# GPS_radiologger_v16.net
KiCad netlist of a schematic drawn in EAGLE
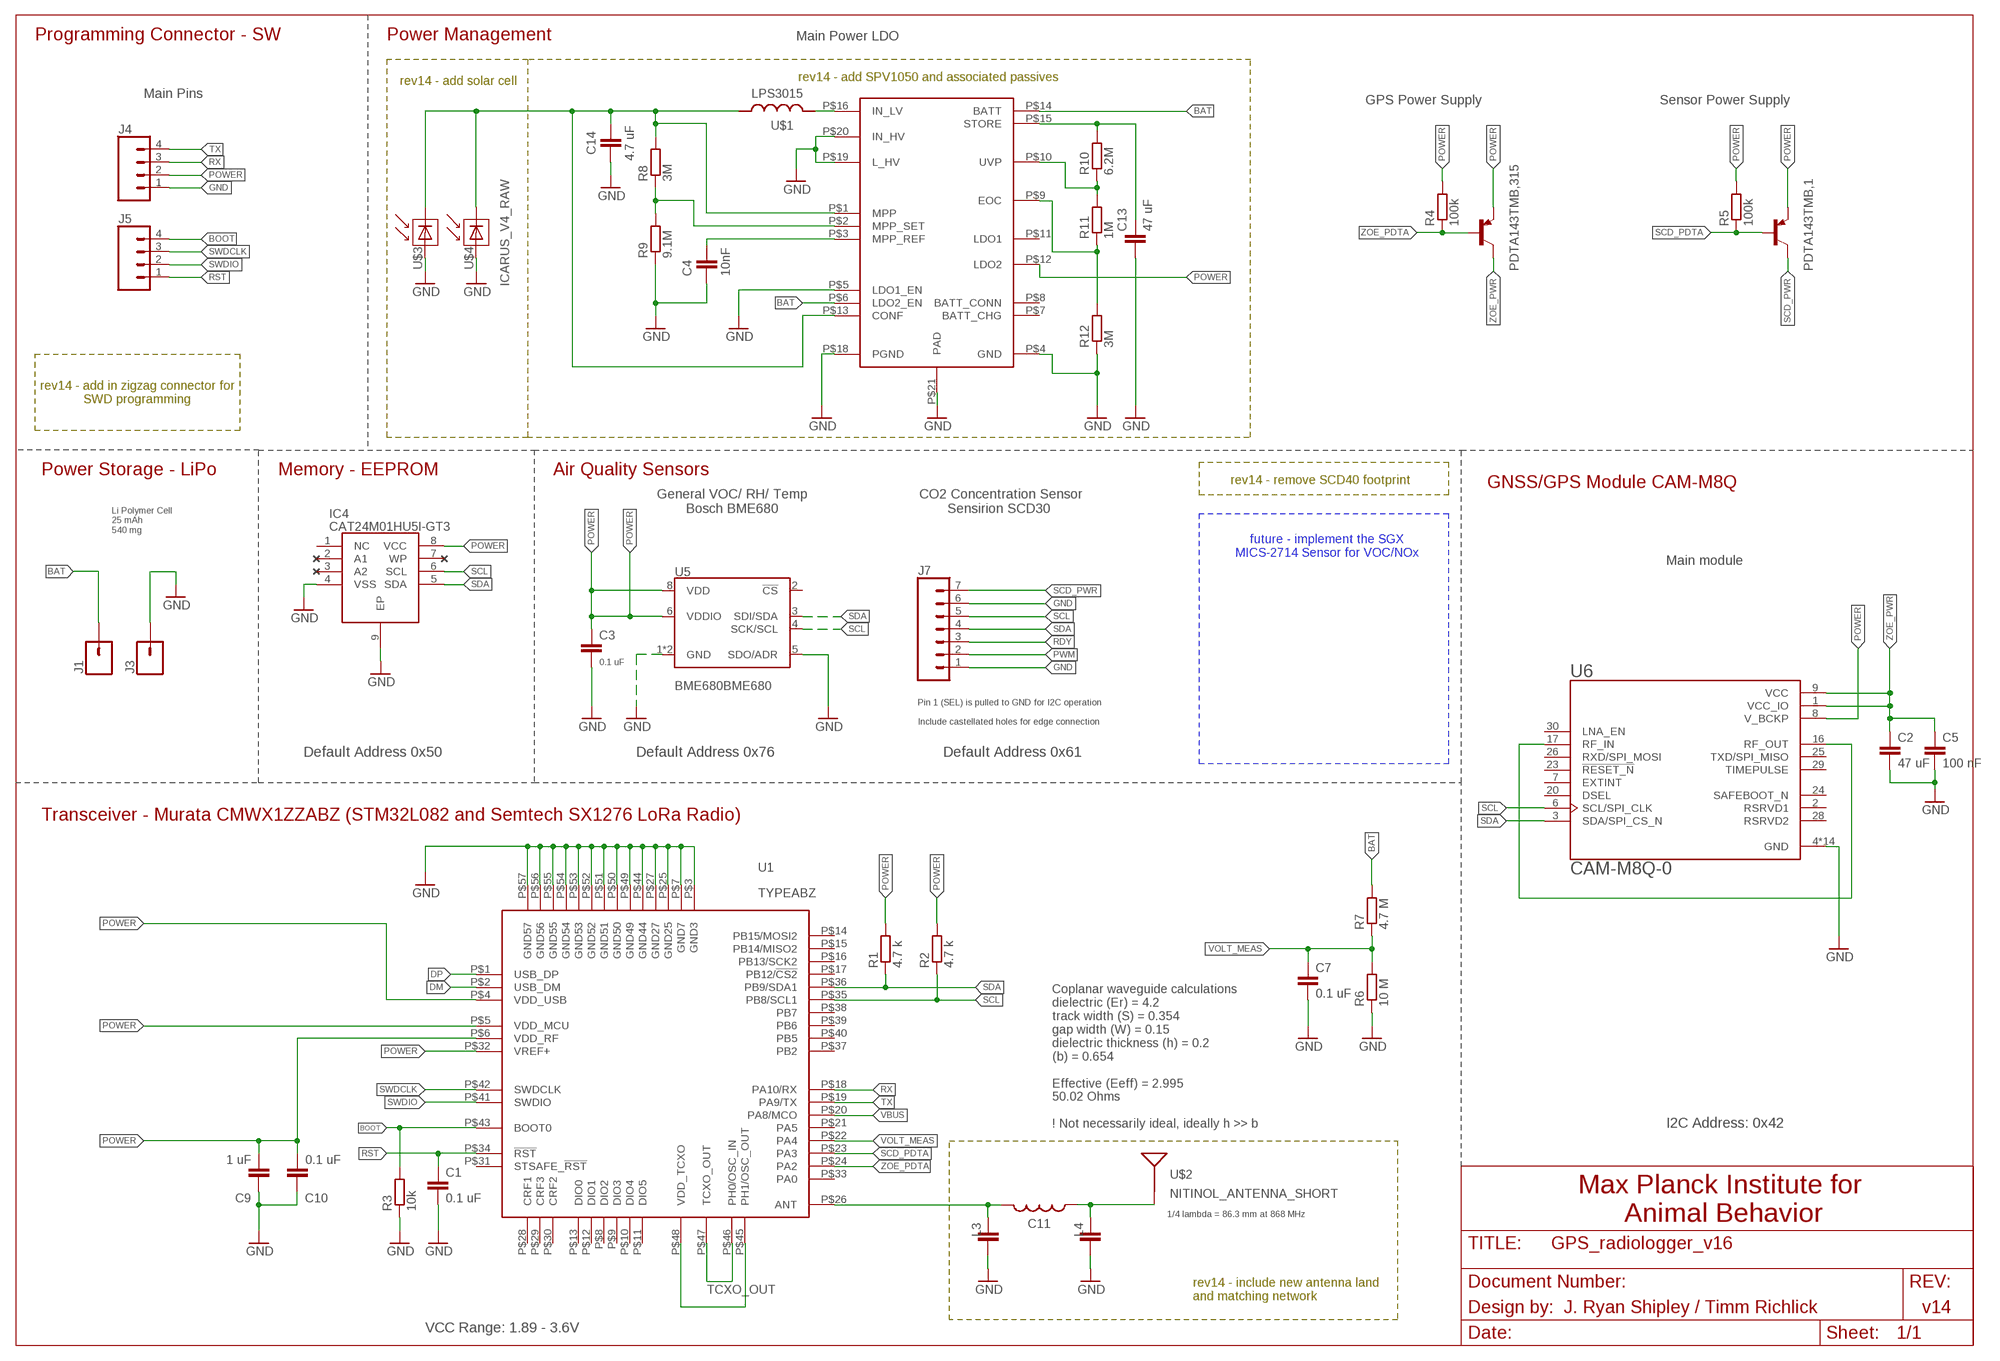
[diagram p0: schematic, sheet 1]

(export (version "E")
  (design (tool "Eeschema 10.0.6"))
  (components
    (comp (ref "C1")
      (value "0.1 uF")
      (footprint "eagle-import:C0201")
      (libsource (lib "eagle-import") (part "C-EUC0201"))
    )
    (comp (ref "C2")
      (value "47 uF")
      (footprint "eagle-import:C0201")
      (libsource (lib "eagle-import") (part "C-EUC0201"))
    )
    (comp (ref "C3")
      (value "0.1 uF")
      (footprint "eagle-import:C0201")
      (libsource (lib "eagle-import") (part "C-EUC0201"))
    )
    (comp (ref "C4")
      (value "10nF")
      (footprint "eagle-import:C0201")
      (libsource (lib "eagle-import") (part "C-EUC0201"))
    )
    (comp (ref "C5")
      (value "100 nF")
      (footprint "eagle-import:C0201")
      (libsource (lib "eagle-import") (part "C-EUC0201"))
    )
    (comp (ref "C7")
      (value "0.1 uF")
      (footprint "eagle-import:C0201")
      (libsource (lib "eagle-import") (part "C-EUC0201"))
    )
    (comp (ref "C9")
      (value "1 uF")
      (footprint "eagle-import:C0201")
      (libsource (lib "eagle-import") (part "C-EUC0201"))
    )
    (comp (ref "C10")
      (value "0.1 uF")
      (footprint "eagle-import:C0201")
      (libsource (lib "eagle-import") (part "C-EUC0201"))
    )
    (comp (ref "C11")
      (value "0.1uF")
      (footprint "eagle-import:L0201")
      (libsource (lib "eagle-import") (part "L-USL0201"))
    )
    (comp (ref "C13")
      (value "47 uF")
      (footprint "eagle-import:C0805K")
      (libsource (lib "eagle-import") (part "C-EUC0805K"))
    )
    (comp (ref "C14")
      (value "4.7 uF")
      (footprint "eagle-import:C0201")
      (libsource (lib "eagle-import") (part "C-EUC0201"))
    )
    (comp (ref "IC4")
      (value "CAT24M01HU5I-GT3")
      (footprint "eagle-import:SON50P300X200X55-9N")
      (fields
        (field (name "MOUSER_PART_NUMBER") "863-CAT24M01HU5I-GT3")
        (field (name "RS_PART_NUMBER") "7814831P")
      )
      (libsource (lib "eagle-import") (part "CAT24M01HU5I-GT3"))
    )
    (comp (ref "J1")
      (value "CONN_01PTH_NO_SILK_YES_STOP")
      (footprint "eagle-import:1X01_NO_SILK")
      (libsource (lib "eagle-import") (part "CONN_01PTH_NO_SILK_YES_STOP"))
    )
    (comp (ref "J3")
      (value "CONN_01PTH_NO_SILK_YES_STOP")
      (footprint "eagle-import:1X01_NO_SILK")
      (libsource (lib "eagle-import") (part "CONN_01PTH_NO_SILK_YES_STOP"))
    )
    (comp (ref "J4")
      (value "CONN_041.27MM_NO_SILK")
      (footprint "eagle-import:1X04_1.27MM_NO_SILK")
      (libsource (lib "eagle-import") (part "CONN_041.27MM_NO_SILK"))
    )
    (comp (ref "J5")
      (value "CONN_041.27MM_NO_SILK")
      (footprint "eagle-import:1X04_1.27MM_NO_SILK")
      (libsource (lib "eagle-import") (part "CONN_041.27MM_NO_SILK"))
    )
    (comp (ref "J7")
      (value "CONN_07NO_SILK")
      (footprint "eagle-import:1X07_NO_SILK")
      (libsource (lib "eagle-import") (part "CONN_07NO_SILK"))
    )
    (comp (ref "L3")
      (value "C-EUC0201")
      (footprint "eagle-import:C0201")
      (libsource (lib "eagle-import") (part "C-EUC0201"))
    )
    (comp (ref "L4")
      (value "C-EUC0201")
      (footprint "eagle-import:C0201")
      (libsource (lib "eagle-import") (part "C-EUC0201"))
    )
    (comp (ref "PDTA143TMB,1")
      (value "TINYPICO-PNPAMB")
      (footprint "eagle-import:SOT883(B)")
      (libsource (lib "eagle-import") (part "TINYPICO-PNPMBA"))
    )
    (comp (ref "PDTA143TMB,315")
      (value "TINYPICO-PNPAMB")
      (footprint "eagle-import:SOT883(B)")
      (libsource (lib "eagle-import") (part "TINYPICO-PNPMBA"))
    )
    (comp (ref "R1")
      (value "4.7 k")
      (footprint "eagle-import:R0201")
      (libsource (lib "eagle-import") (part "R-EU_R0201"))
    )
    (comp (ref "R2")
      (value "4.7 k")
      (footprint "eagle-import:R0201")
      (libsource (lib "eagle-import") (part "R-EU_R0201"))
    )
    (comp (ref "R3")
      (value "10k")
      (footprint "eagle-import:R0201")
      (libsource (lib "eagle-import") (part "R-EU_R0201"))
    )
    (comp (ref "R4")
      (value "100k")
      (footprint "eagle-import:R0201")
      (libsource (lib "eagle-import") (part "R-EU_R0201"))
    )
    (comp (ref "R5")
      (value "100k")
      (footprint "eagle-import:R0201")
      (libsource (lib "eagle-import") (part "R-EU_R0201"))
    )
    (comp (ref "R6")
      (value "10 M")
      (footprint "eagle-import:R0201")
      (libsource (lib "eagle-import") (part "R-EU_R0201"))
    )
    (comp (ref "R7")
      (value "4.7 M")
      (footprint "eagle-import:R0201")
      (libsource (lib "eagle-import") (part "R-EU_R0201"))
    )
    (comp (ref "R8")
      (value "3M")
      (footprint "eagle-import:R0201")
      (libsource (lib "eagle-import") (part "R-EU_R0201"))
    )
    (comp (ref "R9")
      (value "9.1M")
      (footprint "eagle-import:R0201")
      (libsource (lib "eagle-import") (part "R-EU_R0201"))
    )
    (comp (ref "R10")
      (value "6.2M")
      (footprint "eagle-import:R0201")
      (libsource (lib "eagle-import") (part "R-EU_R0201"))
    )
    (comp (ref "R11")
      (value "1M")
      (footprint "eagle-import:R0201")
      (libsource (lib "eagle-import") (part "R-EU_R0201"))
    )
    (comp (ref "R12")
      (value "3M")
      (footprint "eagle-import:R0201")
      (libsource (lib "eagle-import") (part "R-EU_R0201"))
    )
    (comp (ref "U$1")
      (value "LPS3015")
      (footprint "eagle-import:LPS_3015")
      (libsource (lib "eagle-import") (part "LPS3015"))
    )
    (comp (ref "U$2")
      (value "NITINOL_ANTENNA_SHORT")
      (footprint "eagle-import:ICARUS_NITINOL_ANTENNA_SHORT")
      (libsource (lib "eagle-import") (part "NITINOL_ANTENNA_SHORT"))
    )
    (comp (ref "U$3")
      (value "ICARUS_V4_RAW")
      (footprint "eagle-import:ICARUS_FULL_TOP")
      (libsource (lib "eagle-import") (part "ICARUS_V4_RAW"))
    )
    (comp (ref "U$4")
      (value "ICARUS_V4_RAW")
      (footprint "eagle-import:ICARUS_FULL_TOP")
      (libsource (lib "eagle-import") (part "ICARUS_V4_RAW"))
    )
    (comp (ref "U1")
      (value "TYPEABZ")
      (footprint "eagle-import:TYPEABZ")
      (libsource (lib "eagle-import") (part "TYPEABZ"))
    )
    (comp (ref "U4")
      (value "SPV1050")
      (footprint "eagle-import:SPV1050")
      (libsource (lib "eagle-import") (part "SPV1050"))
    )
    (comp (ref "U5")
      (value "BME680BME680")
      (footprint "eagle-import:LGA3.0X3.0")
      (libsource (lib "eagle-import") (part "BME680BME680"))
    )
    (comp (ref "U6")
      (value "CAM-M8Q-0")
      (footprint "eagle-import:LCC100P960X1400X210-31N")
      (fields (field (name "MF") "U-Blox America"))
      (libsource (lib "eagle-import") (part "CAM-M8Q-0"))
    )
  )
  (nets
    (net (code "1") (name "/TCXO_OUT") (class "Default")
      (node (ref "U1") (pin "P$46") (pinfunction "PH0/OSC_IN_P$46") (pintype "bidirectional"))
      (node (ref "U1") (pin "P$47") (pinfunction "TCXO_OUT_P$47") (pintype "bidirectional"))
    )
    (net (code "2") (name "BAT") (class "Default")
      (node (ref "J1") (pin "1") (pinfunction "1_1") (pintype "passive"))
      (node (ref "R7") (pin "2") (pinfunction "2_2") (pintype "passive"))
      (node (ref "U4") (pin "P$14") (pinfunction "BATT_P$14") (pintype "bidirectional"))
      (node (ref "U4") (pin "P$6") (pinfunction "LDO2_EN_P$6") (pintype "input"))
    )
    (net (code "3") (name "BOOT") (class "Default")
      (node (ref "J5") (pin "4") (pinfunction "4_4") (pintype "passive"))
      (node (ref "R3") (pin "2") (pinfunction "2_2") (pintype "passive"))
      (node (ref "U1") (pin "P$43") (pinfunction "BOOT0_P$43") (pintype "bidirectional"))
    )
    (net (code "4") (name "DM") (class "Default")
      (node (ref "U1") (pin "P$2") (pinfunction "USB_DM_P$2") (pintype "bidirectional"))
    )
    (net (code "5") (name "DP") (class "Default")
      (node (ref "U1") (pin "P$1") (pinfunction "USB_DP_P$1") (pintype "bidirectional"))
    )
    (net (code "6") (name "GND") (class "Default")
      (node (ref "C1") (pin "2") (pinfunction "2_2") (pintype "passive"))
      (node (ref "C10") (pin "1") (pinfunction "1_1") (pintype "passive"))
      (node (ref "C13") (pin "2") (pinfunction "2_2") (pintype "passive"))
      (node (ref "C14") (pin "2") (pinfunction "2_2") (pintype "passive"))
      (node (ref "C2") (pin "2") (pinfunction "2_2") (pintype "passive"))
      (node (ref "C3") (pin "2") (pinfunction "2_2") (pintype "passive"))
      (node (ref "C4") (pin "2") (pinfunction "2_2") (pintype "passive"))
      (node (ref "C5") (pin "2") (pinfunction "2_2") (pintype "passive"))
      (node (ref "C7") (pin "2") (pinfunction "2_2") (pintype "passive"))
      (node (ref "C9") (pin "1") (pinfunction "1_1") (pintype "passive"))
      (node (ref "IC4") (pin "4") (pinfunction "VSS_4") (pintype "power_in"))
      (node (ref "IC4") (pin "9") (pinfunction "EP_9") (pintype "bidirectional"))
      (node (ref "J3") (pin "1") (pinfunction "1_1") (pintype "passive"))
      (node (ref "J4") (pin "1") (pinfunction "1_1") (pintype "passive"))
      (node (ref "J7") (pin "1") (pinfunction "1_1") (pintype "passive"))
      (node (ref "J7") (pin "6") (pinfunction "6_6") (pintype "passive"))
      (node (ref "L3") (pin "2") (pinfunction "2_2") (pintype "passive"))
      (node (ref "L4") (pin "2") (pinfunction "2_2") (pintype "passive"))
      (node (ref "R12") (pin "1") (pinfunction "1_1") (pintype "passive"))
      (node (ref "R3") (pin "1") (pinfunction "1_1") (pintype "passive"))
      (node (ref "R6") (pin "1") (pinfunction "1_1") (pintype "passive"))
      (node (ref "R9") (pin "1") (pinfunction "1_1") (pintype "passive"))
      (node (ref "U$3") (pin "P$2") (pinfunction "MINUS_P$2") (pintype "passive"))
      (node (ref "U$4") (pin "P$2") (pinfunction "MINUS_P$2") (pintype "passive"))
      (node (ref "U1") (pin "P$25") (pinfunction "GND25_P$25") (pintype "power_in"))
      (node (ref "U1") (pin "P$27") (pinfunction "GND27_P$27") (pintype "power_in"))
      (node (ref "U1") (pin "P$3") (pinfunction "GND3_P$3") (pintype "power_in"))
      (node (ref "U1") (pin "P$44") (pinfunction "GND44_P$44") (pintype "power_in"))
      (node (ref "U1") (pin "P$49") (pinfunction "GND49_P$49") (pintype "power_in"))
      (node (ref "U1") (pin "P$50") (pinfunction "GND50_P$50") (pintype "power_in"))
      (node (ref "U1") (pin "P$51") (pinfunction "GND51_P$51") (pintype "power_in"))
      (node (ref "U1") (pin "P$52") (pinfunction "GND52_P$52") (pintype "power_in"))
      (node (ref "U1") (pin "P$53") (pinfunction "GND53_P$53") (pintype "power_in"))
      (node (ref "U1") (pin "P$54") (pinfunction "GND54_P$54") (pintype "power_in"))
      (node (ref "U1") (pin "P$55") (pinfunction "GND55_P$55") (pintype "power_in"))
      (node (ref "U1") (pin "P$56") (pinfunction "GND56_P$56") (pintype "power_in"))
      (node (ref "U1") (pin "P$57") (pinfunction "GND57_P$57") (pintype "power_in"))
      (node (ref "U1") (pin "P$7") (pinfunction "GND7_P$7") (pintype "power_in"))
      (node (ref "U4") (pin "P$18") (pinfunction "PGND_P$18") (pintype "power_in"))
      (node (ref "U4") (pin "P$19") (pinfunction "L_HV_P$19") (pintype "power_in"))
      (node (ref "U4") (pin "P$20") (pinfunction "IN_HV_P$20") (pintype "power_in"))
      (node (ref "U4") (pin "P$21") (pinfunction "PAD_P$21") (pintype "power_in"))
      (node (ref "U4") (pin "P$4") (pinfunction "GND_P$4") (pintype "power_in"))
      (node (ref "U4") (pin "P$5") (pinfunction "LDO1_EN_P$5") (pintype "input"))
      (node (ref "U5") (pin "1") (pinfunction "GND_1") (pintype "bidirectional"))
      (node (ref "U5") (pin "5") (pinfunction "SDO/ADR_5") (pintype "bidirectional"))
      (node (ref "U5") (pin "7") (pinfunction "GND_7") (pintype "bidirectional"))
      (node (ref "U6") (pin "10") (pinfunction "GND_10") (pintype "power_in"))
      (node (ref "U6") (pin "11") (pinfunction "GND_11") (pintype "power_in"))
      (node (ref "U6") (pin "12") (pinfunction "GND_12") (pintype "power_in"))
      (node (ref "U6") (pin "13") (pinfunction "GND_13") (pintype "power_in"))
      (node (ref "U6") (pin "14") (pinfunction "GND_14") (pintype "power_in"))
      (node (ref "U6") (pin "15") (pinfunction "GND_15") (pintype "power_in"))
      (node (ref "U6") (pin "18") (pinfunction "GND_18") (pintype "power_in"))
      (node (ref "U6") (pin "19") (pinfunction "GND_19") (pintype "power_in"))
      (node (ref "U6") (pin "21") (pinfunction "GND_21") (pintype "power_in"))
      (node (ref "U6") (pin "22") (pinfunction "GND_22") (pintype "power_in"))
      (node (ref "U6") (pin "27") (pinfunction "GND_27") (pintype "power_in"))
      (node (ref "U6") (pin "31") (pinfunction "GND_31") (pintype "power_in"))
      (node (ref "U6") (pin "4") (pinfunction "GND_4") (pintype "power_in"))
      (node (ref "U6") (pin "5") (pinfunction "GND_5") (pintype "power_in"))
    )
    (net (code "7") (name "Net-(C11-Pad1)") (class "Default")
      (node (ref "C11") (pin "1") (pinfunction "1_1") (pintype "passive"))
      (node (ref "L4") (pin "1") (pinfunction "1_1") (pintype "passive"))
      (node (ref "U$2") (pin "1") (pinfunction "SIGNAL_1") (pintype "bidirectional"))
      (node (ref "U$2") (pin "2") (pinfunction "SIGNAL_2") (pintype "bidirectional"))
      (node (ref "U$2") (pin "3") (pinfunction "SIGNAL_3") (pintype "bidirectional"))
    )
    (net (code "8") (name "Net-(U$1-1)") (class "Default")
      (node (ref "C14") (pin "1") (pinfunction "1_1") (pintype "passive"))
      (node (ref "R8") (pin "2") (pinfunction "2_2") (pintype "passive"))
      (node (ref "U$1") (pin "P$1") (pinfunction "1_P$1") (pintype "passive"))
      (node (ref "U$3") (pin "P$1") (pinfunction "PLUS_P$1") (pintype "passive"))
      (node (ref "U$4") (pin "P$1") (pinfunction "PLUS_P$1") (pintype "passive"))
      (node (ref "U4") (pin "P$1") (pinfunction "MPP_P$1") (pintype "input"))
      (node (ref "U4") (pin "P$13") (pinfunction "CONF_P$13") (pintype "input"))
    )
    (net (code "9") (name "Net-(U$1-2)") (class "Default")
      (node (ref "U$1") (pin "P$2") (pinfunction "2_P$2") (pintype "passive"))
      (node (ref "U4") (pin "P$16") (pinfunction "IN_LV_P$16") (pintype "power_in"))
    )
    (net (code "10") (name "Net-(U1-ANT)") (class "Default")
      (node (ref "C11") (pin "2") (pinfunction "2_2") (pintype "passive"))
      (node (ref "L3") (pin "1") (pinfunction "1_1") (pintype "passive"))
      (node (ref "U1") (pin "P$26") (pinfunction "ANT_P$26") (pintype "bidirectional"))
    )
    (net (code "11") (name "Net-(U1-PH1{slash}OSC_OUT)") (class "Default")
      (node (ref "U1") (pin "P$45") (pinfunction "PH1/OSC_OUT_P$45") (pintype "bidirectional"))
      (node (ref "U1") (pin "P$48") (pinfunction "VDD_TCXO_P$48") (pintype "power_in"))
    )
    (net (code "12") (name "Net-(U4-EOC)") (class "Default")
      (node (ref "R11") (pin "1") (pinfunction "1_1") (pintype "passive"))
      (node (ref "R12") (pin "2") (pinfunction "2_2") (pintype "passive"))
      (node (ref "U4") (pin "P$9") (pinfunction "EOC_P$9") (pintype "input"))
    )
    (net (code "13") (name "Net-(U4-MPP_REF)") (class "Default")
      (node (ref "C4") (pin "1") (pinfunction "1_1") (pintype "passive"))
      (node (ref "U4") (pin "P$3") (pinfunction "MPP_REF_P$3") (pintype "input"))
    )
    (net (code "14") (name "Net-(U4-MPP_SET)") (class "Default")
      (node (ref "R8") (pin "1") (pinfunction "1_1") (pintype "passive"))
      (node (ref "R9") (pin "2") (pinfunction "2_2") (pintype "passive"))
      (node (ref "U4") (pin "P$2") (pinfunction "MPP_SET_P$2") (pintype "input"))
    )
    (net (code "15") (name "Net-(U4-STORE)") (class "Default")
      (node (ref "C13") (pin "1") (pinfunction "1_1") (pintype "passive"))
      (node (ref "R10") (pin "2") (pinfunction "2_2") (pintype "passive"))
      (node (ref "U4") (pin "P$15") (pinfunction "STORE_P$15") (pintype "bidirectional"))
    )
    (net (code "16") (name "Net-(U4-UVP)") (class "Default")
      (node (ref "R10") (pin "1") (pinfunction "1_1") (pintype "passive"))
      (node (ref "R11") (pin "2") (pinfunction "2_2") (pintype "passive"))
      (node (ref "U4") (pin "P$10") (pinfunction "UVP_P$10") (pintype "input"))
    )
    (net (code "17") (name "Net-(U6-RF_IN)") (class "Default")
      (node (ref "U6") (pin "16") (pinfunction "RF_OUT_16") (pintype "output"))
      (node (ref "U6") (pin "17") (pinfunction "RF_IN_17") (pintype "input"))
    )
    (net (code "18") (name "POWER") (class "Default")
      (node (ref "C10") (pin "2") (pinfunction "2_2") (pintype "passive"))
      (node (ref "C3") (pin "1") (pinfunction "1_1") (pintype "passive"))
      (node (ref "C9") (pin "2") (pinfunction "2_2") (pintype "passive"))
      (node (ref "IC4") (pin "8") (pinfunction "VCC_8") (pintype "power_in"))
      (node (ref "J4") (pin "2") (pinfunction "2_2") (pintype "passive"))
      (node (ref "PDTA143TMB,1") (pin "2") (pinfunction "E_2") (pintype "passive"))
      (node (ref "PDTA143TMB,315") (pin "2") (pinfunction "E_2") (pintype "passive"))
      (node (ref "R1") (pin "2") (pinfunction "2_2") (pintype "passive"))
      (node (ref "R2") (pin "2") (pinfunction "2_2") (pintype "passive"))
      (node (ref "R4") (pin "2") (pinfunction "2_2") (pintype "passive"))
      (node (ref "R5") (pin "2") (pinfunction "2_2") (pintype "passive"))
      (node (ref "U1") (pin "P$32") (pinfunction "VREF+_P$32") (pintype "power_in"))
      (node (ref "U1") (pin "P$4") (pinfunction "VDD_USB_P$4") (pintype "power_in"))
      (node (ref "U1") (pin "P$5") (pinfunction "VDD_MCU_P$5") (pintype "power_in"))
      (node (ref "U1") (pin "P$6") (pinfunction "VDD_RF_P$6") (pintype "power_in"))
      (node (ref "U4") (pin "P$12") (pinfunction "LDO2_P$12") (pintype "output"))
      (node (ref "U5") (pin "6") (pinfunction "VDDIO_6") (pintype "bidirectional"))
      (node (ref "U5") (pin "8") (pinfunction "VDD_8") (pintype "bidirectional"))
      (node (ref "U6") (pin "8") (pinfunction "V_BCKP_8") (pintype "power_in"))
    )
    (net (code "19") (name "PWM") (class "Default")
      (node (ref "J7") (pin "2") (pinfunction "2_2") (pintype "passive"))
    )
    (net (code "20") (name "RDY") (class "Default")
      (node (ref "J7") (pin "3") (pinfunction "3_3") (pintype "passive"))
    )
    (net (code "21") (name "RST") (class "Default")
      (node (ref "C1") (pin "1") (pinfunction "1_1") (pintype "passive"))
      (node (ref "J5") (pin "1") (pinfunction "1_1") (pintype "passive"))
      (node (ref "U1") (pin "P$34") (pinfunction "~{RST}_P$34") (pintype "bidirectional"))
    )
    (net (code "22") (name "RX") (class "Default")
      (node (ref "J4") (pin "3") (pinfunction "3_3") (pintype "passive"))
      (node (ref "U1") (pin "P$18") (pinfunction "PA10/RX_P$18") (pintype "bidirectional"))
    )
    (net (code "23") (name "SCD_PDTA") (class "Default")
      (node (ref "PDTA143TMB,1") (pin "1") (pinfunction "B_1") (pintype "passive"))
      (node (ref "R5") (pin "1") (pinfunction "1_1") (pintype "passive"))
      (node (ref "U1") (pin "P$23") (pinfunction "PA3_P$23") (pintype "bidirectional"))
    )
    (net (code "24") (name "SCD_PWR") (class "Default")
      (node (ref "J7") (pin "7") (pinfunction "7_7") (pintype "passive"))
      (node (ref "PDTA143TMB,1") (pin "3") (pinfunction "C_3") (pintype "passive"))
    )
    (net (code "25") (name "SCL") (class "Default")
      (node (ref "IC4") (pin "6") (pinfunction "SCL_6") (pintype "bidirectional"))
      (node (ref "J7") (pin "5") (pinfunction "5_5") (pintype "passive"))
      (node (ref "R2") (pin "1") (pinfunction "1_1") (pintype "passive"))
      (node (ref "U1") (pin "P$35") (pinfunction "PB8/SCL1_P$35") (pintype "bidirectional"))
      (node (ref "U5") (pin "4") (pinfunction "SCK/SCL_4") (pintype "bidirectional"))
      (node (ref "U6") (pin "6") (pinfunction "SCL/SPI_CLK_6") (pintype "input"))
    )
    (net (code "26") (name "SDA") (class "Default")
      (node (ref "IC4") (pin "5") (pinfunction "SDA_5") (pintype "bidirectional"))
      (node (ref "J7") (pin "4") (pinfunction "4_4") (pintype "passive"))
      (node (ref "R1") (pin "1") (pinfunction "1_1") (pintype "passive"))
      (node (ref "U1") (pin "P$36") (pinfunction "PB9/SDA1_P$36") (pintype "bidirectional"))
      (node (ref "U5") (pin "3") (pinfunction "SDI/SDA_3") (pintype "bidirectional"))
      (node (ref "U6") (pin "3") (pinfunction "SDA/SPI_CS_N_3") (pintype "bidirectional"))
    )
    (net (code "27") (name "SWDCLK") (class "Default")
      (node (ref "J5") (pin "3") (pinfunction "3_3") (pintype "passive"))
      (node (ref "U1") (pin "P$42") (pinfunction "SWDCLK_P$42") (pintype "bidirectional"))
    )
    (net (code "28") (name "SWDIO") (class "Default")
      (node (ref "J5") (pin "2") (pinfunction "2_2") (pintype "passive"))
      (node (ref "U1") (pin "P$41") (pinfunction "SWDIO_P$41") (pintype "bidirectional"))
    )
    (net (code "29") (name "TX") (class "Default")
      (node (ref "J4") (pin "4") (pinfunction "4_4") (pintype "passive"))
      (node (ref "U1") (pin "P$19") (pinfunction "PA9/TX_P$19") (pintype "bidirectional"))
    )
    (net (code "30") (name "VBUS") (class "Default")
      (node (ref "U1") (pin "P$20") (pinfunction "PA8/MCO_P$20") (pintype "bidirectional"))
    )
    (net (code "31") (name "VOLT_MEAS") (class "Default")
      (node (ref "C7") (pin "1") (pinfunction "1_1") (pintype "passive"))
      (node (ref "R6") (pin "2") (pinfunction "2_2") (pintype "passive"))
      (node (ref "R7") (pin "1") (pinfunction "1_1") (pintype "passive"))
      (node (ref "U1") (pin "P$22") (pinfunction "PA4_P$22") (pintype "bidirectional"))
    )
    (net (code "32") (name "ZOE_PDTA") (class "Default")
      (node (ref "PDTA143TMB,315") (pin "1") (pinfunction "B_1") (pintype "passive"))
      (node (ref "R4") (pin "1") (pinfunction "1_1") (pintype "passive"))
      (node (ref "U1") (pin "P$24") (pinfunction "PA2_P$24") (pintype "bidirectional"))
    )
    (net (code "33") (name "ZOE_PWR") (class "Default")
      (node (ref "C2") (pin "1") (pinfunction "1_1") (pintype "passive"))
      (node (ref "C5") (pin "1") (pinfunction "1_1") (pintype "passive"))
      (node (ref "PDTA143TMB,315") (pin "3") (pinfunction "C_3") (pintype "passive"))
      (node (ref "U6") (pin "1") (pinfunction "VCC_IO_1") (pintype "power_in"))
      (node (ref "U6") (pin "9") (pinfunction "VCC_9") (pintype "power_in"))
    )
    (net (code "34") (name "unconnected-(IC4-A1-Pad2)") (class "Default")
      (node (ref "IC4") (pin "2") (pinfunction "A1_2") (pintype "bidirectional"))
    )
    (net (code "35") (name "unconnected-(IC4-A2-Pad3)") (class "Default")
      (node (ref "IC4") (pin "3") (pinfunction "A2_3") (pintype "bidirectional"))
    )
    (net (code "36") (name "unconnected-(IC4-NC-Pad1)") (class "Default")
      (node (ref "IC4") (pin "1") (pinfunction "NC_1") (pintype "no_connect"))
    )
    (net (code "37") (name "unconnected-(IC4-WP-Pad7)") (class "Default")
      (node (ref "IC4") (pin "7") (pinfunction "WP_7") (pintype "bidirectional"))
    )
    (net (code "38") (name "unconnected-(U1-CRF1-PadP$28)") (class "Default")
      (node (ref "U1") (pin "P$28") (pinfunction "CRF1_P$28") (pintype "no_connect"))
    )
    (net (code "39") (name "unconnected-(U1-CRF2-PadP$30)") (class "Default")
      (node (ref "U1") (pin "P$30") (pinfunction "CRF2_P$30") (pintype "no_connect"))
    )
    (net (code "40") (name "unconnected-(U1-CRF3-PadP$29)") (class "Default")
      (node (ref "U1") (pin "P$29") (pinfunction "CRF3_P$29") (pintype "no_connect"))
    )
    (net (code "41") (name "unconnected-(U1-DIO0-PadP$13)") (class "Default")
      (node (ref "U1") (pin "P$13") (pinfunction "DIO0_P$13") (pintype "no_connect"))
    )
    (net (code "42") (name "unconnected-(U1-DIO1-PadP$12)") (class "Default")
      (node (ref "U1") (pin "P$12") (pinfunction "DIO1_P$12") (pintype "no_connect"))
    )
    (net (code "43") (name "unconnected-(U1-DIO2-PadP$8)") (class "Default")
      (node (ref "U1") (pin "P$8") (pinfunction "DIO2_P$8") (pintype "no_connect"))
    )
    (net (code "44") (name "unconnected-(U1-DIO3-PadP$9)") (class "Default")
      (node (ref "U1") (pin "P$9") (pinfunction "DIO3_P$9") (pintype "no_connect"))
    )
    (net (code "45") (name "unconnected-(U1-DIO4-PadP$10)") (class "Default")
      (node (ref "U1") (pin "P$10") (pinfunction "DIO4_P$10") (pintype "bidirectional"))
    )
    (net (code "46") (name "unconnected-(U1-DIO5-PadP$11)") (class "Default")
      (node (ref "U1") (pin "P$11") (pinfunction "DIO5_P$11") (pintype "bidirectional"))
    )
    (net (code "47") (name "unconnected-(U1-PA0-PadP$33)") (class "Default")
      (node (ref "U1") (pin "P$33") (pinfunction "PA0_P$33") (pintype "bidirectional"))
    )
    (net (code "48") (name "unconnected-(U1-PA5-PadP$21)") (class "Default")
      (node (ref "U1") (pin "P$21") (pinfunction "PA5_P$21") (pintype "bidirectional"))
    )
    (net (code "49") (name "unconnected-(U1-PB2-PadP$37)") (class "Default")
      (node (ref "U1") (pin "P$37") (pinfunction "PB2_P$37") (pintype "bidirectional"))
    )
    (net (code "50") (name "unconnected-(U1-PB5-PadP$40)") (class "Default")
      (node (ref "U1") (pin "P$40") (pinfunction "PB5_P$40") (pintype "bidirectional"))
    )
    (net (code "51") (name "unconnected-(U1-PB6-PadP$39)") (class "Default")
      (node (ref "U1") (pin "P$39") (pinfunction "PB6_P$39") (pintype "bidirectional"))
    )
    (net (code "52") (name "unconnected-(U1-PB7-PadP$38)") (class "Default")
      (node (ref "U1") (pin "P$38") (pinfunction "PB7_P$38") (pintype "bidirectional"))
    )
    (net (code "53") (name "unconnected-(U1-PB12{slash}~{CS2}-PadP$17)") (class "Default")
      (node (ref "U1") (pin "P$17") (pinfunction "PB12/~{CS2}_P$17") (pintype "bidirectional"))
    )
    (net (code "54") (name "unconnected-(U1-PB13{slash}SCK2-PadP$16)") (class "Default")
      (node (ref "U1") (pin "P$16") (pinfunction "PB13/SCK2_P$16") (pintype "bidirectional"))
    )
    (net (code "55") (name "unconnected-(U1-PB14{slash}MISO2-PadP$15)") (class "Default")
      (node (ref "U1") (pin "P$15") (pinfunction "PB14/MISO2_P$15") (pintype "bidirectional"))
    )
    (net (code "56") (name "unconnected-(U1-PB15{slash}MOSI2-PadP$14)") (class "Default")
      (node (ref "U1") (pin "P$14") (pinfunction "PB15/MOSI2_P$14") (pintype "bidirectional"))
    )
    (net (code "57") (name "unconnected-(U1-STSAFE_~{RST}-PadP$31)") (class "Default")
      (node (ref "U1") (pin "P$31") (pinfunction "STSAFE_~{RST}_P$31") (pintype "bidirectional"))
    )
    (net (code "58") (name "unconnected-(U4-BATT_CHG-PadP$7)") (class "Default")
      (node (ref "U4") (pin "P$7") (pinfunction "BATT_CHG_P$7") (pintype "open_collector"))
    )
    (net (code "59") (name "unconnected-(U4-BATT_CONN-PadP$8)") (class "Default")
      (node (ref "U4") (pin "P$8") (pinfunction "BATT_CONN_P$8") (pintype "open_collector"))
    )
    (net (code "60") (name "unconnected-(U4-LDO1-PadP$11)") (class "Default")
      (node (ref "U4") (pin "P$11") (pinfunction "LDO1_P$11") (pintype "output"))
    )
    (net (code "61") (name "unconnected-(U5-~{CS}-Pad2)") (class "Default")
      (node (ref "U5") (pin "2") (pinfunction "~{CS}_2") (pintype "bidirectional"))
    )
    (net (code "62") (name "unconnected-(U6-DSEL-Pad20)") (class "Default")
      (node (ref "U6") (pin "20") (pinfunction "DSEL_20") (pintype "input"))
    )
    (net (code "63") (name "unconnected-(U6-EXTINT-Pad7)") (class "Default")
      (node (ref "U6") (pin "7") (pinfunction "EXTINT_7") (pintype "input"))
    )
    (net (code "64") (name "unconnected-(U6-LNA_EN-Pad30)") (class "Default")
      (node (ref "U6") (pin "30") (pinfunction "LNA_EN_30") (pintype "input"))
    )
    (net (code "65") (name "unconnected-(U6-RSRVD1-Pad2)") (class "Default")
      (node (ref "U6") (pin "2") (pinfunction "RSRVD1_2") (pintype "passive"))
    )
    (net (code "66") (name "unconnected-(U6-RSRVD2-Pad28)") (class "Default")
      (node (ref "U6") (pin "28") (pinfunction "RSRVD2_28") (pintype "passive"))
    )
    (net (code "67") (name "unconnected-(U6-RXD{slash}SPI_MOSI-Pad26)") (class "Default")
      (node (ref "U6") (pin "26") (pinfunction "RXD/SPI_MOSI_26") (pintype "input"))
    )
    (net (code "68") (name "unconnected-(U6-SAFEBOOT_N-Pad24)") (class "Default")
      (node (ref "U6") (pin "24") (pinfunction "SAFEBOOT_N_24") (pintype "passive"))
    )
    (net (code "69") (name "unconnected-(U6-TIMEPULSE-Pad29)") (class "Default")
      (node (ref "U6") (pin "29") (pinfunction "TIMEPULSE_29") (pintype "output"))
    )
    (net (code "70") (name "unconnected-(U6-TXD{slash}SPI_MISO-Pad25)") (class "Default")
      (node (ref "U6") (pin "25") (pinfunction "TXD/SPI_MISO_25") (pintype "output"))
    )
    (net (code "71") (name "unconnected-(U6-~{RESET_N}-Pad23)") (class "Default")
      (node (ref "U6") (pin "23") (pinfunction "~{RESET_N}_23") (pintype "input"))
    )
  )
)
